# Connector.net
KiCad netlist of a schematic drawn in Altium Designer
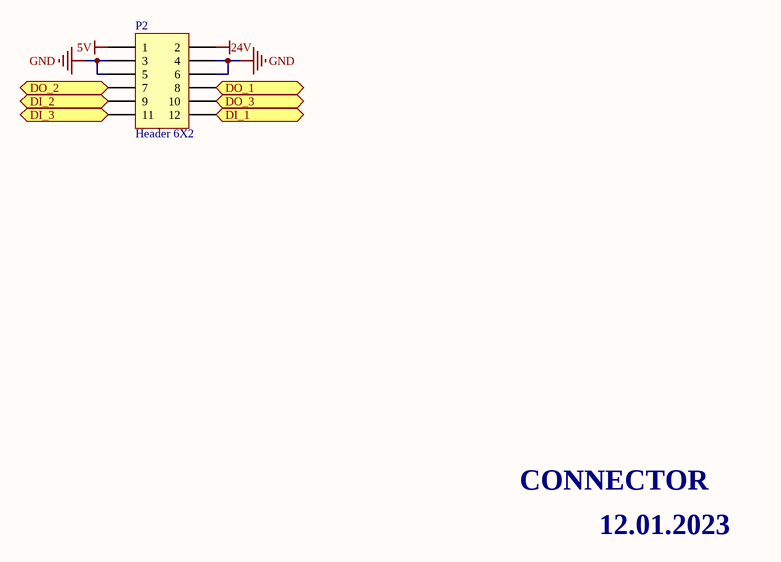
[diagram p0: Connector.SchDoc]

(export (version "E")
  (design (tool "Eeschema 10.0.6"))
  (components
    (comp (ref "P2")
      (value "Header 6X2")
      (footprint "HDR2X6")
      (description "CONNECTOR Header, 6-Pin, Dual row")
      (fields (field (name "PUBLISHER") "Altium Limited"))
      (libsource (lib "geolib") (part "Header 6X2"))
    )
  )
  (nets
    (net (code "1") (name "/DI_1") (class "Default")
      (node (ref "P2") (pin "12") (pinfunction "12_12") (pintype "passive"))
    )
    (net (code "2") (name "/DI_2") (class "Default")
      (node (ref "P2") (pin "9") (pinfunction "9_9") (pintype "passive"))
    )
    (net (code "3") (name "/DI_3") (class "Default")
      (node (ref "P2") (pin "11") (pinfunction "11_11") (pintype "passive"))
    )
    (net (code "4") (name "/DO_1") (class "Default")
      (node (ref "P2") (pin "8") (pinfunction "8_8") (pintype "passive"))
    )
    (net (code "5") (name "/DO_2") (class "Default")
      (node (ref "P2") (pin "7") (pinfunction "7_7") (pintype "passive"))
    )
    (net (code "6") (name "/DO_3") (class "Default")
      (node (ref "P2") (pin "10") (pinfunction "10_10") (pintype "passive"))
    )
    (net (code "7") (name "5V") (class "Default")
      (node (ref "P2") (pin "1") (pinfunction "1_1") (pintype "passive"))
    )
    (net (code "8") (name "24V") (class "Default")
      (node (ref "P2") (pin "2") (pinfunction "2_2") (pintype "passive"))
    )
    (net (code "9") (name "GND") (class "Default")
      (node (ref "P2") (pin "3") (pinfunction "3_3") (pintype "passive"))
      (node (ref "P2") (pin "4") (pinfunction "4_4") (pintype "passive"))
      (node (ref "P2") (pin "5") (pinfunction "5_5") (pintype "passive"))
      (node (ref "P2") (pin "6") (pinfunction "6_6") (pintype "passive"))
    )
  )
)
